# AVEFlex.net
KiCad netlist of a schematic drawn in EAGLE
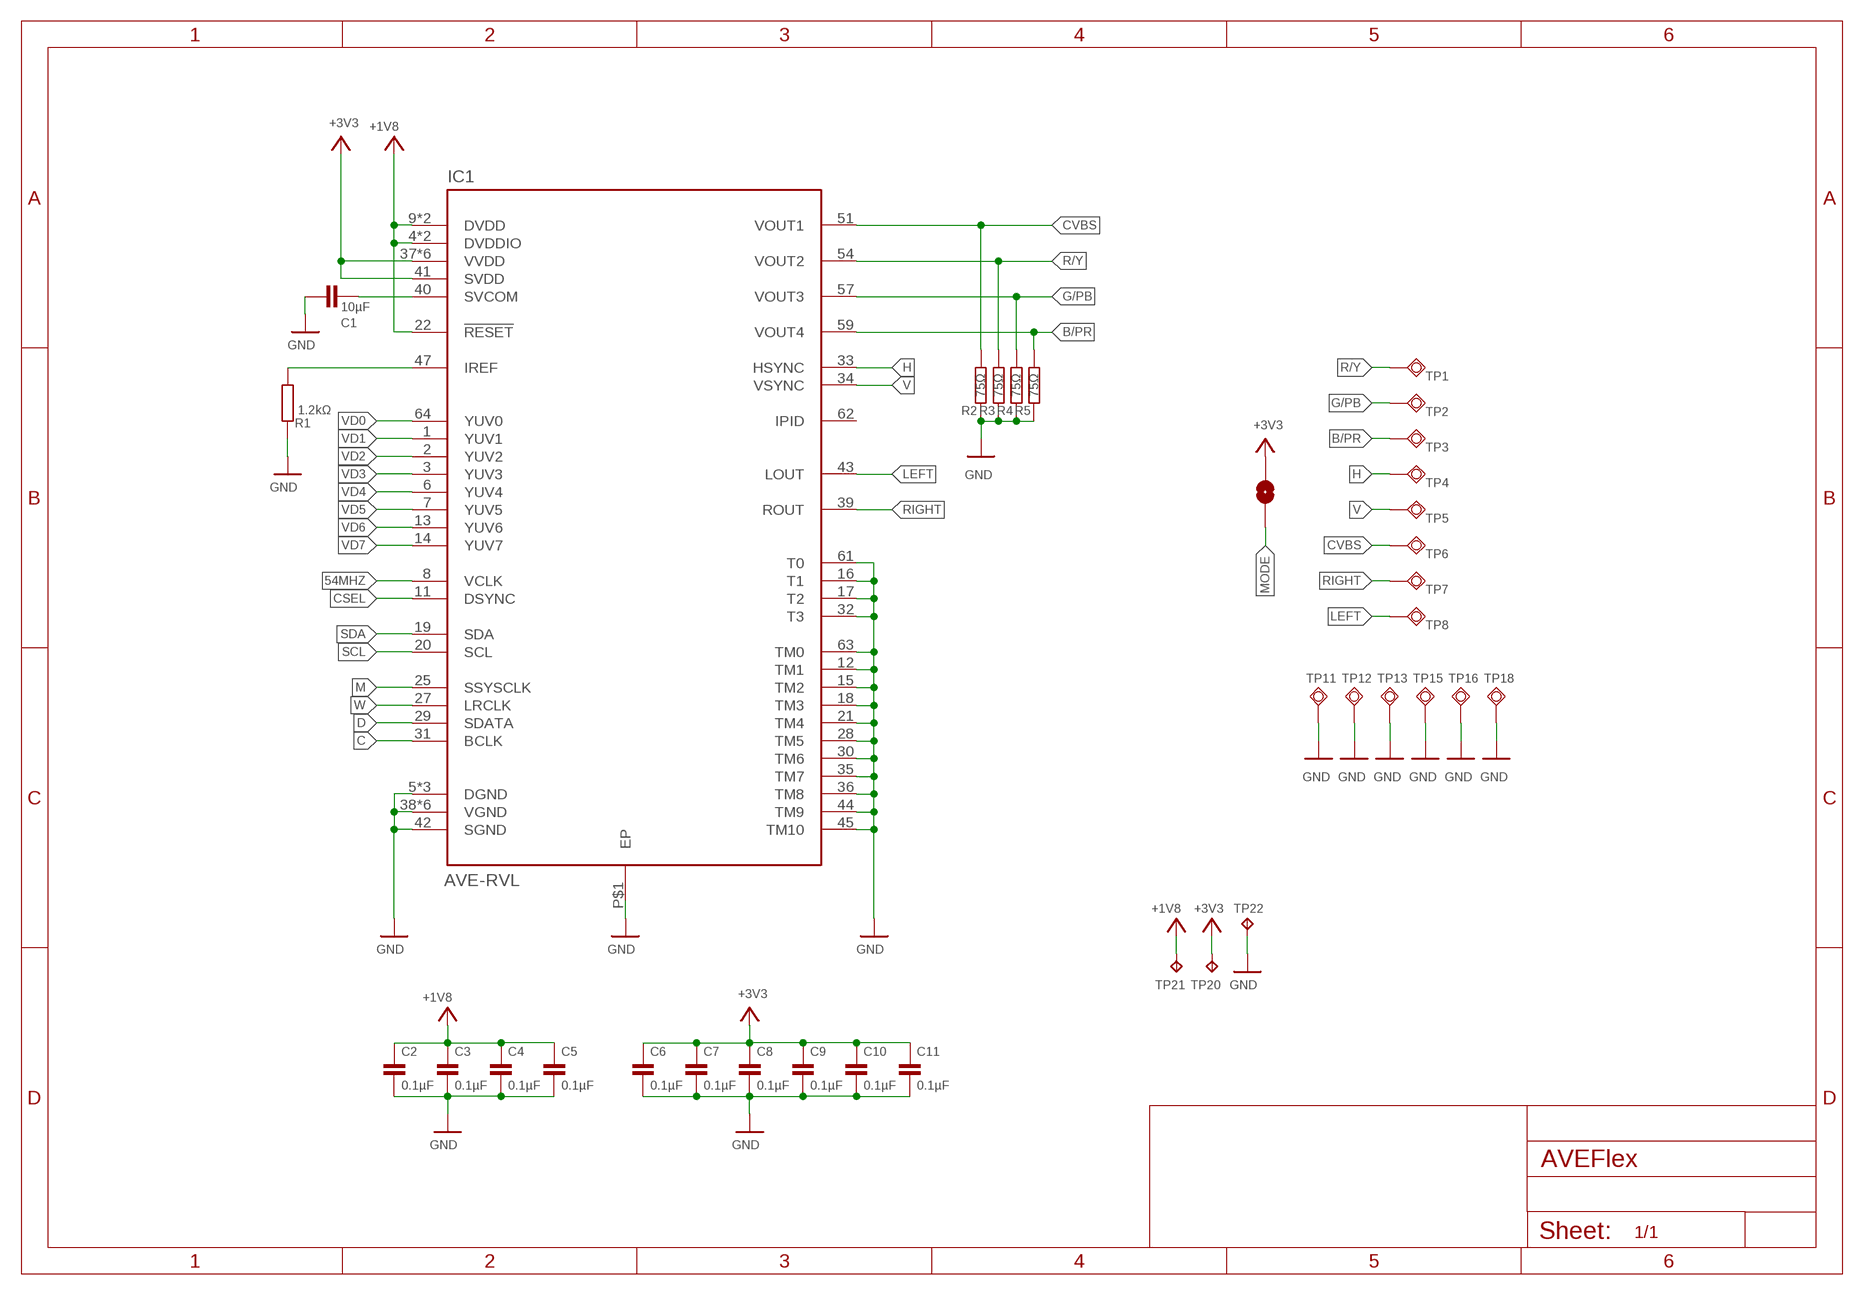
[diagram p0: schematic, sheet 1]

(export (version "E")
  (design (tool "Eeschema 10.0.6"))
  (components
    (comp (ref "C1")
      (value "10µF")
      (footprint "eagle-import:C0603")
      (libsource (lib "eagle-import") (part "C-USC0603"))
    )
    (comp (ref "C2")
      (value "0.1µF")
      (footprint "eagle-import:C0402")
      (libsource (lib "eagle-import") (part "C-USC0402"))
    )
    (comp (ref "C3")
      (value "0.1µF")
      (footprint "eagle-import:C0402")
      (libsource (lib "eagle-import") (part "C-USC0402"))
    )
    (comp (ref "C4")
      (value "0.1µF")
      (footprint "eagle-import:C0402")
      (libsource (lib "eagle-import") (part "C-USC0402"))
    )
    (comp (ref "C5")
      (value "0.1µF")
      (footprint "eagle-import:C0402")
      (libsource (lib "eagle-import") (part "C-USC0402"))
    )
    (comp (ref "C6")
      (value "0.1µF")
      (footprint "eagle-import:C0402")
      (libsource (lib "eagle-import") (part "C-USC0402"))
    )
    (comp (ref "C7")
      (value "0.1µF")
      (footprint "eagle-import:C0402")
      (libsource (lib "eagle-import") (part "C-USC0402"))
    )
    (comp (ref "C8")
      (value "0.1µF")
      (footprint "eagle-import:C0402")
      (libsource (lib "eagle-import") (part "C-USC0402"))
    )
    (comp (ref "C9")
      (value "0.1µF")
      (footprint "eagle-import:C0402")
      (libsource (lib "eagle-import") (part "C-USC0402"))
    )
    (comp (ref "C10")
      (value "0.1µF")
      (footprint "eagle-import:C0402")
      (libsource (lib "eagle-import") (part "C-USC0402"))
    )
    (comp (ref "C11")
      (value "0.1µF")
      (footprint "eagle-import:C0402")
      (libsource (lib "eagle-import") (part "C-USC0402"))
    )
    (comp (ref "IC1")
      (value "AVE-RVL")
      (footprint "eagle-import:TQFP64-10X10")
      (libsource (lib "eagle-import") (part "AVE"))
    )
    (comp (ref "JP1")
      (value "JUMPER-SMT_2_NO_SILK")
      (footprint "eagle-import:SMT-JUMPER_2_NO_SILK")
      (libsource (lib "eagle-import") (part "JUMPER-SMT_2_NO_SILK"))
    )
    (comp (ref "R1")
      (value "1.2kΩ")
      (footprint "eagle-import:R0402")
      (libsource (lib "eagle-import") (part "R-US_R0402"))
    )
    (comp (ref "R2")
      (value "75Ω")
      (footprint "eagle-import:R0402")
      (libsource (lib "eagle-import") (part "R-US_R0402"))
    )
    (comp (ref "R3")
      (value "75Ω")
      (footprint "eagle-import:R0402")
      (libsource (lib "eagle-import") (part "R-US_R0402"))
    )
    (comp (ref "R4")
      (value "75Ω")
      (footprint "eagle-import:R0402")
      (libsource (lib "eagle-import") (part "R-US_R0402"))
    )
    (comp (ref "R5")
      (value "75Ω")
      (footprint "eagle-import:R0402")
      (libsource (lib "eagle-import") (part "R-US_R0402"))
    )
    (comp (ref "TP1")
      (value "TPSQTP10R")
      (footprint "eagle-import:TP10R")
      (libsource (lib "eagle-import") (part "TPSQTP10R"))
    )
    (comp (ref "TP2")
      (value "TPSQTP10R")
      (footprint "eagle-import:TP10R")
      (libsource (lib "eagle-import") (part "TPSQTP10R"))
    )
    (comp (ref "TP3")
      (value "TPSQTP10R")
      (footprint "eagle-import:TP10R")
      (libsource (lib "eagle-import") (part "TPSQTP10R"))
    )
    (comp (ref "TP4")
      (value "TPSQTP10R")
      (footprint "eagle-import:TP10R")
      (libsource (lib "eagle-import") (part "TPSQTP10R"))
    )
    (comp (ref "TP5")
      (value "TPSQTP10R")
      (footprint "eagle-import:TP10R")
      (libsource (lib "eagle-import") (part "TPSQTP10R"))
    )
    (comp (ref "TP6")
      (value "TPSQTP10R")
      (footprint "eagle-import:TP10R")
      (libsource (lib "eagle-import") (part "TPSQTP10R"))
    )
    (comp (ref "TP7")
      (value "TPSQTP10R")
      (footprint "eagle-import:TP10R")
      (libsource (lib "eagle-import") (part "TPSQTP10R"))
    )
    (comp (ref "TP8")
      (value "TPSQTP10R")
      (footprint "eagle-import:TP10R")
      (libsource (lib "eagle-import") (part "TPSQTP10R"))
    )
    (comp (ref "TP11")
      (value "TPSQTP10R")
      (footprint "eagle-import:TP10R")
      (libsource (lib "eagle-import") (part "TPSQTP10R"))
    )
    (comp (ref "TP12")
      (value "TPSQTP10R")
      (footprint "eagle-import:TP10R")
      (libsource (lib "eagle-import") (part "TPSQTP10R"))
    )
    (comp (ref "TP13")
      (value "TPSQTP10R")
      (footprint "eagle-import:TP10R")
      (libsource (lib "eagle-import") (part "TPSQTP10R"))
    )
    (comp (ref "TP15")
      (value "TPSQTP10R")
      (footprint "eagle-import:TP10R")
      (libsource (lib "eagle-import") (part "TPSQTP10R"))
    )
    (comp (ref "TP16")
      (value "TPSQTP10R")
      (footprint "eagle-import:TP10R")
      (libsource (lib "eagle-import") (part "TPSQTP10R"))
    )
    (comp (ref "TP18")
      (value "TPSQTP10R")
      (footprint "eagle-import:TP10R")
      (libsource (lib "eagle-import") (part "TPSQTP10R"))
    )
    (comp (ref "TP20")
      (value "TPTP10SQ")
      (footprint "eagle-import:TP10SQ")
      (libsource (lib "eagle-import") (part "TPTP10SQ"))
    )
    (comp (ref "TP21")
      (value "TPTP10SQ")
      (footprint "eagle-import:TP10SQ")
      (libsource (lib "eagle-import") (part "TPTP10SQ"))
    )
    (comp (ref "TP22")
      (value "TPTP10SQ")
      (footprint "eagle-import:TP10SQ")
      (libsource (lib "eagle-import") (part "TPTP10SQ"))
    )
  )
  (nets
    (net (code "1") (name "+1V8") (class "Default")
      (node (ref "C2") (pin "1") (pinfunction "1_1") (pintype "passive"))
      (node (ref "C3") (pin "1") (pinfunction "1_1") (pintype "passive"))
      (node (ref "C4") (pin "1") (pinfunction "1_1") (pintype "passive"))
      (node (ref "C5") (pin "1") (pinfunction "1_1") (pintype "passive"))
      (node (ref "IC1") (pin "22") (pinfunction "~{RESET}_22") (pintype "bidirectional"))
      (node (ref "IC1") (pin "23") (pinfunction "DVDD_23") (pintype "bidirectional"))
      (node (ref "IC1") (pin "26") (pinfunction "DVDDIO_26") (pintype "bidirectional"))
      (node (ref "IC1") (pin "4") (pinfunction "DVDDIO_4") (pintype "bidirectional"))
      (node (ref "IC1") (pin "9") (pinfunction "DVDD_9") (pintype "bidirectional"))
      (node (ref "TP21") (pin "TP") (pinfunction "TP_TP") (pintype "input"))
    )
    (net (code "2") (name "+3V3") (class "Default")
      (node (ref "C10") (pin "1") (pinfunction "1_1") (pintype "passive"))
      (node (ref "C11") (pin "1") (pinfunction "1_1") (pintype "passive"))
      (node (ref "C6") (pin "1") (pinfunction "1_1") (pintype "passive"))
      (node (ref "C7") (pin "1") (pinfunction "1_1") (pintype "passive"))
      (node (ref "C8") (pin "1") (pinfunction "1_1") (pintype "passive"))
      (node (ref "C9") (pin "1") (pinfunction "1_1") (pintype "passive"))
      (node (ref "IC1") (pin "37") (pinfunction "VVDD_37") (pintype "bidirectional"))
      (node (ref "IC1") (pin "41") (pinfunction "SVDD_41") (pintype "bidirectional"))
      (node (ref "IC1") (pin "46") (pinfunction "VVDD_46") (pintype "bidirectional"))
      (node (ref "IC1") (pin "50") (pinfunction "VVDD_50") (pintype "bidirectional"))
      (node (ref "IC1") (pin "53") (pinfunction "VVDD_53") (pintype "bidirectional"))
      (node (ref "IC1") (pin "56") (pinfunction "VVDD_56") (pintype "bidirectional"))
      (node (ref "IC1") (pin "60") (pinfunction "VVDD_60") (pintype "bidirectional"))
      (node (ref "JP1") (pin "2") (pinfunction "2_2") (pintype "passive"))
      (node (ref "TP20") (pin "TP") (pinfunction "TP_TP") (pintype "input"))
    )
    (net (code "3") (name "54MHZ") (class "Default")
      (node (ref "IC1") (pin "8") (pinfunction "VCLK_8") (pintype "bidirectional"))
    )
    (net (code "4") (name "B{slash}PR") (class "Default")
      (node (ref "IC1") (pin "59") (pinfunction "VOUT4_59") (pintype "bidirectional"))
      (node (ref "R5") (pin "1") (pinfunction "1_1") (pintype "passive"))
      (node (ref "TP3") (pin "TP") (pinfunction "TP_TP") (pintype "input"))
    )
    (net (code "5") (name "C") (class "Default")
      (node (ref "IC1") (pin "31") (pinfunction "BCLK_31") (pintype "bidirectional"))
    )
    (net (code "6") (name "CSEL") (class "Default")
      (node (ref "IC1") (pin "11") (pinfunction "DSYNC_11") (pintype "bidirectional"))
    )
    (net (code "7") (name "CVBS") (class "Default")
      (node (ref "IC1") (pin "51") (pinfunction "VOUT1_51") (pintype "bidirectional"))
      (node (ref "R2") (pin "1") (pinfunction "1_1") (pintype "passive"))
      (node (ref "TP6") (pin "TP") (pinfunction "TP_TP") (pintype "input"))
    )
    (net (code "8") (name "D") (class "Default")
      (node (ref "IC1") (pin "29") (pinfunction "SDATA_29") (pintype "bidirectional"))
    )
    (net (code "9") (name "GND") (class "Default")
      (node (ref "C1") (pin "2") (pinfunction "2_2") (pintype "passive"))
      (node (ref "C10") (pin "2") (pinfunction "2_2") (pintype "passive"))
      (node (ref "C11") (pin "2") (pinfunction "2_2") (pintype "passive"))
      (node (ref "C2") (pin "2") (pinfunction "2_2") (pintype "passive"))
      (node (ref "C3") (pin "2") (pinfunction "2_2") (pintype "passive"))
      (node (ref "C4") (pin "2") (pinfunction "2_2") (pintype "passive"))
      (node (ref "C5") (pin "2") (pinfunction "2_2") (pintype "passive"))
      (node (ref "C6") (pin "2") (pinfunction "2_2") (pintype "passive"))
      (node (ref "C7") (pin "2") (pinfunction "2_2") (pintype "passive"))
      (node (ref "C8") (pin "2") (pinfunction "2_2") (pintype "passive"))
      (node (ref "C9") (pin "2") (pinfunction "2_2") (pintype "passive"))
      (node (ref "IC1") (pin "10") (pinfunction "DGND_10") (pintype "bidirectional"))
      (node (ref "IC1") (pin "12") (pinfunction "TM1_12") (pintype "bidirectional"))
      (node (ref "IC1") (pin "15") (pinfunction "TM2_15") (pintype "bidirectional"))
      (node (ref "IC1") (pin "16") (pinfunction "T1_16") (pintype "bidirectional"))
      (node (ref "IC1") (pin "17") (pinfunction "T2_17") (pintype "bidirectional"))
      (node (ref "IC1") (pin "18") (pinfunction "TM3_18") (pintype "bidirectional"))
      (node (ref "IC1") (pin "21") (pinfunction "TM4_21") (pintype "bidirectional"))
      (node (ref "IC1") (pin "24") (pinfunction "DGND_24") (pintype "bidirectional"))
      (node (ref "IC1") (pin "28") (pinfunction "TM5_28") (pintype "bidirectional"))
      (node (ref "IC1") (pin "30") (pinfunction "TM6_30") (pintype "bidirectional"))
      (node (ref "IC1") (pin "32") (pinfunction "T3_32") (pintype "bidirectional"))
      (node (ref "IC1") (pin "35") (pinfunction "TM7_35") (pintype "bidirectional"))
      (node (ref "IC1") (pin "36") (pinfunction "TM8_36") (pintype "bidirectional"))
      (node (ref "IC1") (pin "38") (pinfunction "VGND_38") (pintype "bidirectional"))
      (node (ref "IC1") (pin "42") (pinfunction "SGND_42") (pintype "bidirectional"))
      (node (ref "IC1") (pin "44") (pinfunction "TM9_44") (pintype "bidirectional"))
      (node (ref "IC1") (pin "45") (pinfunction "TM10_45") (pintype "bidirectional"))
      (node (ref "IC1") (pin "48") (pinfunction "VGND_48") (pintype "bidirectional"))
      (node (ref "IC1") (pin "49") (pinfunction "VGND_49") (pintype "bidirectional"))
      (node (ref "IC1") (pin "5") (pinfunction "DGND_5") (pintype "bidirectional"))
      (node (ref "IC1") (pin "52") (pinfunction "VGND_52") (pintype "bidirectional"))
      (node (ref "IC1") (pin "55") (pinfunction "VGND_55") (pintype "bidirectional"))
      (node (ref "IC1") (pin "58") (pinfunction "VGND_58") (pintype "bidirectional"))
      (node (ref "IC1") (pin "61") (pinfunction "T0_61") (pintype "bidirectional"))
      (node (ref "IC1") (pin "63") (pinfunction "TM0_63") (pintype "bidirectional"))
      (node (ref "IC1") (pin "P$1") (pinfunction "EP_P$1") (pintype "bidirectional"))
      (node (ref "R1") (pin "2") (pinfunction "2_2") (pintype "passive"))
      (node (ref "R2") (pin "2") (pinfunction "2_2") (pintype "passive"))
      (node (ref "R3") (pin "2") (pinfunction "2_2") (pintype "passive"))
      (node (ref "R4") (pin "2") (pinfunction "2_2") (pintype "passive"))
      (node (ref "R5") (pin "2") (pinfunction "2_2") (pintype "passive"))
      (node (ref "TP11") (pin "TP") (pinfunction "TP_TP") (pintype "input"))
      (node (ref "TP12") (pin "TP") (pinfunction "TP_TP") (pintype "input"))
      (node (ref "TP13") (pin "TP") (pinfunction "TP_TP") (pintype "input"))
      (node (ref "TP15") (pin "TP") (pinfunction "TP_TP") (pintype "input"))
      (node (ref "TP16") (pin "TP") (pinfunction "TP_TP") (pintype "input"))
      (node (ref "TP18") (pin "TP") (pinfunction "TP_TP") (pintype "input"))
      (node (ref "TP22") (pin "TP") (pinfunction "TP_TP") (pintype "input"))
    )
    (net (code "10") (name "G{slash}PB") (class "Default")
      (node (ref "IC1") (pin "57") (pinfunction "VOUT3_57") (pintype "bidirectional"))
      (node (ref "R4") (pin "1") (pinfunction "1_1") (pintype "passive"))
      (node (ref "TP2") (pin "TP") (pinfunction "TP_TP") (pintype "input"))
    )
    (net (code "11") (name "H") (class "Default")
      (node (ref "IC1") (pin "33") (pinfunction "HSYNC_33") (pintype "bidirectional"))
      (node (ref "TP4") (pin "TP") (pinfunction "TP_TP") (pintype "input"))
    )
    (net (code "12") (name "LEFT") (class "Default")
      (node (ref "IC1") (pin "43") (pinfunction "LOUT_43") (pintype "bidirectional"))
      (node (ref "TP8") (pin "TP") (pinfunction "TP_TP") (pintype "input"))
    )
    (net (code "13") (name "M") (class "Default")
      (node (ref "IC1") (pin "25") (pinfunction "SSYSCLK_25") (pintype "bidirectional"))
    )
    (net (code "14") (name "MODE") (class "Default")
      (node (ref "JP1") (pin "1") (pinfunction "1_1") (pintype "passive"))
    )
    (net (code "15") (name "Net-(IC1-IREF)") (class "Default")
      (node (ref "IC1") (pin "47") (pinfunction "IREF_47") (pintype "bidirectional"))
      (node (ref "R1") (pin "1") (pinfunction "1_1") (pintype "passive"))
    )
    (net (code "16") (name "Net-(IC1-SVCOM)") (class "Default")
      (node (ref "C1") (pin "1") (pinfunction "1_1") (pintype "passive"))
      (node (ref "IC1") (pin "40") (pinfunction "SVCOM_40") (pintype "bidirectional"))
    )
    (net (code "17") (name "RIGHT") (class "Default")
      (node (ref "IC1") (pin "39") (pinfunction "ROUT_39") (pintype "bidirectional"))
      (node (ref "TP7") (pin "TP") (pinfunction "TP_TP") (pintype "input"))
    )
    (net (code "18") (name "R{slash}Y") (class "Default")
      (node (ref "IC1") (pin "54") (pinfunction "VOUT2_54") (pintype "bidirectional"))
      (node (ref "R3") (pin "1") (pinfunction "1_1") (pintype "passive"))
      (node (ref "TP1") (pin "TP") (pinfunction "TP_TP") (pintype "input"))
    )
    (net (code "19") (name "SCL") (class "Default")
      (node (ref "IC1") (pin "20") (pinfunction "SCL_20") (pintype "bidirectional"))
    )
    (net (code "20") (name "SDA") (class "Default")
      (node (ref "IC1") (pin "19") (pinfunction "SDA_19") (pintype "bidirectional"))
    )
    (net (code "21") (name "V") (class "Default")
      (node (ref "IC1") (pin "34") (pinfunction "VSYNC_34") (pintype "bidirectional"))
      (node (ref "TP5") (pin "TP") (pinfunction "TP_TP") (pintype "input"))
    )
    (net (code "22") (name "VD0") (class "Default")
      (node (ref "IC1") (pin "64") (pinfunction "YUV0_64") (pintype "bidirectional"))
    )
    (net (code "23") (name "VD1") (class "Default")
      (node (ref "IC1") (pin "1") (pinfunction "YUV1_1") (pintype "bidirectional"))
    )
    (net (code "24") (name "VD2") (class "Default")
      (node (ref "IC1") (pin "2") (pinfunction "YUV2_2") (pintype "bidirectional"))
    )
    (net (code "25") (name "VD3") (class "Default")
      (node (ref "IC1") (pin "3") (pinfunction "YUV3_3") (pintype "bidirectional"))
    )
    (net (code "26") (name "VD4") (class "Default")
      (node (ref "IC1") (pin "6") (pinfunction "YUV4_6") (pintype "bidirectional"))
    )
    (net (code "27") (name "VD5") (class "Default")
      (node (ref "IC1") (pin "7") (pinfunction "YUV5_7") (pintype "bidirectional"))
    )
    (net (code "28") (name "VD6") (class "Default")
      (node (ref "IC1") (pin "13") (pinfunction "YUV6_13") (pintype "bidirectional"))
    )
    (net (code "29") (name "VD7") (class "Default")
      (node (ref "IC1") (pin "14") (pinfunction "YUV7_14") (pintype "bidirectional"))
    )
    (net (code "30") (name "W") (class "Default")
      (node (ref "IC1") (pin "27") (pinfunction "LRCLK_27") (pintype "bidirectional"))
    )
    (net (code "31") (name "unconnected-(IC1-IPID-Pad62)") (class "Default")
      (node (ref "IC1") (pin "62") (pinfunction "IPID_62") (pintype "bidirectional"))
    )
  )
)
